# level_shifter.net
KiCad netlist of a schematic drawn in Altium Designer
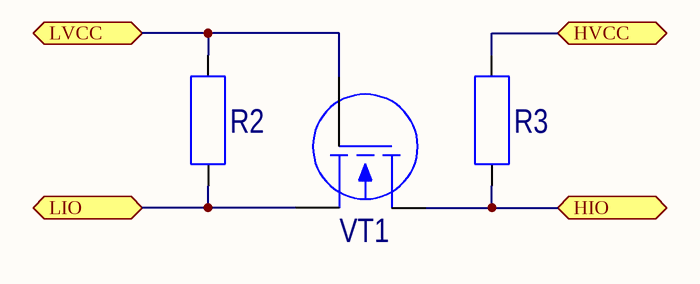
[diagram p0: level shifter.SchDoc]

(export (version "E")
  (design (tool "Eeschema 10.0.6"))
  (components
    (comp (ref "R2")
      (value "10K0603")
      (footprint "RESC1608X06N/0603")
      (description "RES SMD 10K OHM 1% 1/8W 0603")
      (fields
        (field (name "MANUFACTURER PART NUMBER") "MCT06030C1002FP500")
        (field (name "MANUFACTURER") "Vishay Beyschlag")
      )
      (libsource (lib "R") (part "10K0603"))
    )
    (comp (ref "R3")
      (value "10K0603")
      (footprint "RESC1608X06N/0603")
      (description "RES SMD 10K OHM 1% 1/8W 0603")
      (fields
        (field (name "MANUFACTURER PART NUMBER") "MCT06030C1002FP500")
        (field (name "MANUFACTURER") "Vishay Beyschlag")
      )
      (libsource (lib "R") (part "10K0603"))
    )
    (comp (ref "VT1")
      (value "IRLML6244TRPBF")
      (footprint "TP-236 (SOT23)")
      (description "MOSFET N-CH 20V 6.3A SOT-23")
      (fields (field (name "MANUFACTURER") "Infineon Technologies"))
      (libsource (lib "VT") (part "IRLML6244TRPBF"))
    )
  )
  (nets
    (net (code "1") (name "/HIO") (class "Default")
      (node (ref "R3") (pin "1") (pinfunction "1_1") (pintype "passive"))
      (node (ref "VT1") (pin "3") (pinfunction "3_3") (pintype "passive"))
    )
    (net (code "2") (name "/HVCC") (class "Default")
      (node (ref "R3") (pin "2") (pinfunction "2_2") (pintype "passive"))
    )
    (net (code "3") (name "/LIO") (class "Default")
      (node (ref "R2") (pin "1") (pinfunction "1_1") (pintype "passive"))
      (node (ref "VT1") (pin "2") (pinfunction "2_2") (pintype "passive"))
    )
    (net (code "4") (name "/LVCC") (class "Default")
      (node (ref "R2") (pin "2") (pinfunction "2_2") (pintype "passive"))
      (node (ref "VT1") (pin "1") (pinfunction "1_1") (pintype "passive"))
    )
  )
)
